# weddingbot.net
KiCad netlist of a schematic drawn in EAGLE
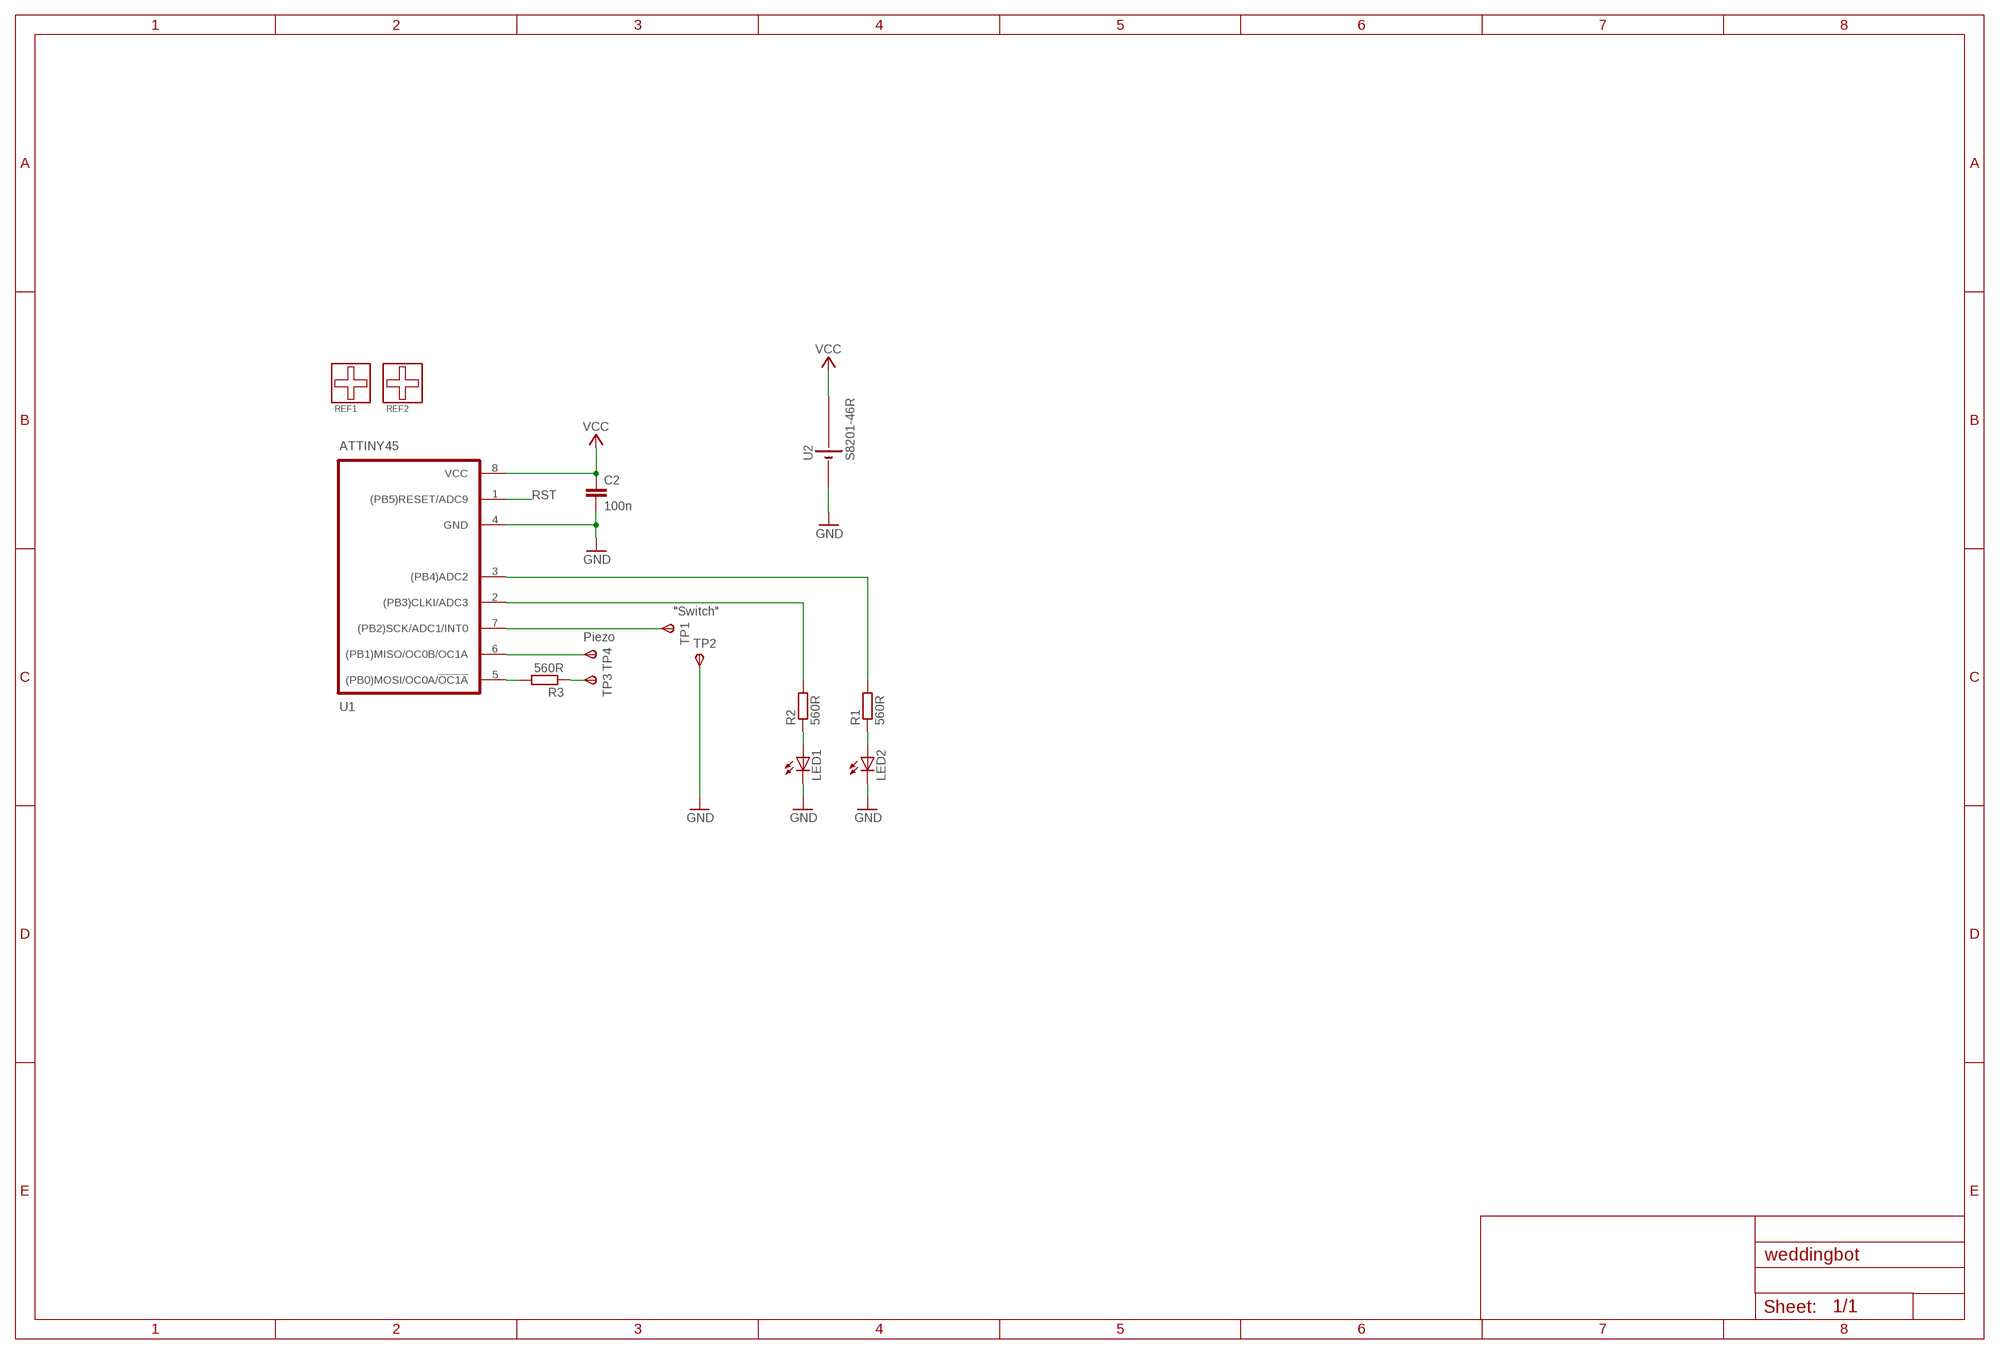
[diagram p0: schematic, sheet 1]

(export (version "E")
  (design (tool "Eeschema 10.0.6"))
  (components
    (comp (ref "C2")
      (value "100n")
      (footprint "eagle-import:C0603")
      (libsource (lib "eagle-import") (part "C-EUC0603"))
    )
    (comp (ref "LED1")
      (value "LEDMEINE")
      (footprint "eagle-import:CHIPLED_REV_1206")
      (libsource (lib "eagle-import") (part "LEDMEINE"))
    )
    (comp (ref "LED2")
      (value "LEDMEINE")
      (footprint "eagle-import:CHIPLED_REV_1206")
      (libsource (lib "eagle-import") (part "LEDMEINE"))
    )
    (comp (ref "R1")
      (value "560R")
      (footprint "eagle-import:R0603")
      (libsource (lib "eagle-import") (part "R-EU_R0603"))
    )
    (comp (ref "R2")
      (value "560R")
      (footprint "eagle-import:R0603")
      (libsource (lib "eagle-import") (part "R-EU_R0603"))
    )
    (comp (ref "R3")
      (value "560R")
      (footprint "eagle-import:R0603")
      (libsource (lib "eagle-import") (part "R-EU_R0603"))
    )
    (comp (ref "REF1")
      (value "FIDUCIAL_ROUND")
      (footprint "eagle-import:REF_ROUND")
      (libsource (lib "eagle-import") (part "FIDUCIAL_ROUND"))
    )
    (comp (ref "REF2")
      (value "FIDUCIAL_ROUND")
      (footprint "eagle-import:REF_ROUND")
      (libsource (lib "eagle-import") (part "FIDUCIAL_ROUND"))
    )
    (comp (ref "TP1")
      (value "TPSTP20R")
      (footprint "eagle-import:TP20R")
      (libsource (lib "eagle-import") (part "TPSTP20R"))
    )
    (comp (ref "TP2")
      (value "TPSTP20R")
      (footprint "eagle-import:TP20R")
      (libsource (lib "eagle-import") (part "TPSTP20R"))
    )
    (comp (ref "TP3")
      (value "TPSTP20R")
      (footprint "eagle-import:TP20R")
      (libsource (lib "eagle-import") (part "TPSTP20R"))
    )
    (comp (ref "TP4")
      (value "TPSTP20R")
      (footprint "eagle-import:TP20R")
      (libsource (lib "eagle-import") (part "TPSTP20R"))
    )
    (comp (ref "U1")
      (value "ATTINY45")
      (footprint "eagle-import:SOIC8")
      (libsource (lib "eagle-import") (part "ATTINY45"))
    )
    (comp (ref "U2")
      (value "S8201-46R")
      (footprint "eagle-import:S8201-46R")
      (libsource (lib "eagle-import") (part "S8201-46R"))
    )
  )
  (nets
    (net (code "1") (name "/RST") (class "Default")
      (node (ref "U1") (pin "1") (pinfunction "(PB5)RESET/ADC9_1") (pintype "bidirectional"))
    )
    (net (code "2") (name "GND") (class "Default")
      (node (ref "C2") (pin "2") (pinfunction "2_2") (pintype "passive"))
      (node (ref "LED1") (pin "C") (pinfunction "C_C") (pintype "passive"))
      (node (ref "LED2") (pin "C") (pinfunction "C_C") (pintype "passive"))
      (node (ref "TP2") (pin "TP") (pinfunction "PP_TP") (pintype "input"))
      (node (ref "U1") (pin "4") (pinfunction "GND_4") (pintype "power_in"))
      (node (ref "U2") (pin "P1") (pinfunction "GND_P1") (pintype "bidirectional"))
    )
    (net (code "3") (name "Net-(LED1-PadA)") (class "Default")
      (node (ref "LED1") (pin "A") (pinfunction "A_A") (pintype "passive"))
      (node (ref "R2") (pin "1") (pinfunction "1_1") (pintype "passive"))
    )
    (net (code "4") (name "Net-(LED2-PadA)") (class "Default")
      (node (ref "LED2") (pin "A") (pinfunction "A_A") (pintype "passive"))
      (node (ref "R1") (pin "1") (pinfunction "1_1") (pintype "passive"))
    )
    (net (code "5") (name "Net-(TP1-PP)") (class "Default")
      (node (ref "TP1") (pin "TP") (pinfunction "PP_TP") (pintype "input"))
      (node (ref "U1") (pin "7") (pinfunction "(PB2)SCK/ADC1/INT0_7") (pintype "bidirectional"))
    )
    (net (code "6") (name "Net-(TP3-PP)") (class "Default")
      (node (ref "R3") (pin "1") (pinfunction "1_1") (pintype "passive"))
      (node (ref "TP3") (pin "TP") (pinfunction "PP_TP") (pintype "input"))
    )
    (net (code "7") (name "Net-(TP4-PP)") (class "Default")
      (node (ref "TP4") (pin "TP") (pinfunction "PP_TP") (pintype "input"))
      (node (ref "U1") (pin "6") (pinfunction "(PB1)MISO/OC0B/OC1A_6") (pintype "bidirectional"))
    )
    (net (code "8") (name "Net-(U1-(PB0)MOSI{slash}OC0A{slash}~{OC1A})") (class "Default")
      (node (ref "R3") (pin "2") (pinfunction "2_2") (pintype "passive"))
      (node (ref "U1") (pin "5") (pinfunction "(PB0)MOSI/OC0A/~{OC1A}_5") (pintype "bidirectional"))
    )
    (net (code "9") (name "Net-(U1-(PB3)CLKI{slash}ADC3)") (class "Default")
      (node (ref "R2") (pin "2") (pinfunction "2_2") (pintype "passive"))
      (node (ref "U1") (pin "2") (pinfunction "(PB3)CLKI/ADC3_2") (pintype "bidirectional"))
    )
    (net (code "10") (name "Net-(U1-(PB4)ADC2)") (class "Default")
      (node (ref "R1") (pin "2") (pinfunction "2_2") (pintype "passive"))
      (node (ref "U1") (pin "3") (pinfunction "(PB4)ADC2_3") (pintype "bidirectional"))
    )
    (net (code "11") (name "VCC") (class "Default")
      (node (ref "C2") (pin "1") (pinfunction "1_1") (pintype "passive"))
      (node (ref "U1") (pin "8") (pinfunction "VCC_8") (pintype "power_in"))
      (node (ref "U2") (pin "P2") (pinfunction "VV1_P2") (pintype "bidirectional"))
    )
    (net (code "12") (name "unconnected-(REF1-PadP$1)") (class "Default")
      (node (ref "REF1") (pin "P$1") (pinfunction "P$1_P$1") (pintype "passive"))
    )
    (net (code "13") (name "unconnected-(REF2-PadP$1)") (class "Default")
      (node (ref "REF2") (pin "P$1") (pinfunction "P$1_P$1") (pintype "passive"))
    )
    (net (code "14") (name "unconnected-(U2-VV2-PadP3)") (class "Default")
      (node (ref "U2") (pin "P3") (pinfunction "VV2_P3") (pintype "bidirectional"))
    )
  )
)
